# DCDC_2_rev3.net
KiCad netlist of a schematic drawn in Altium Designer
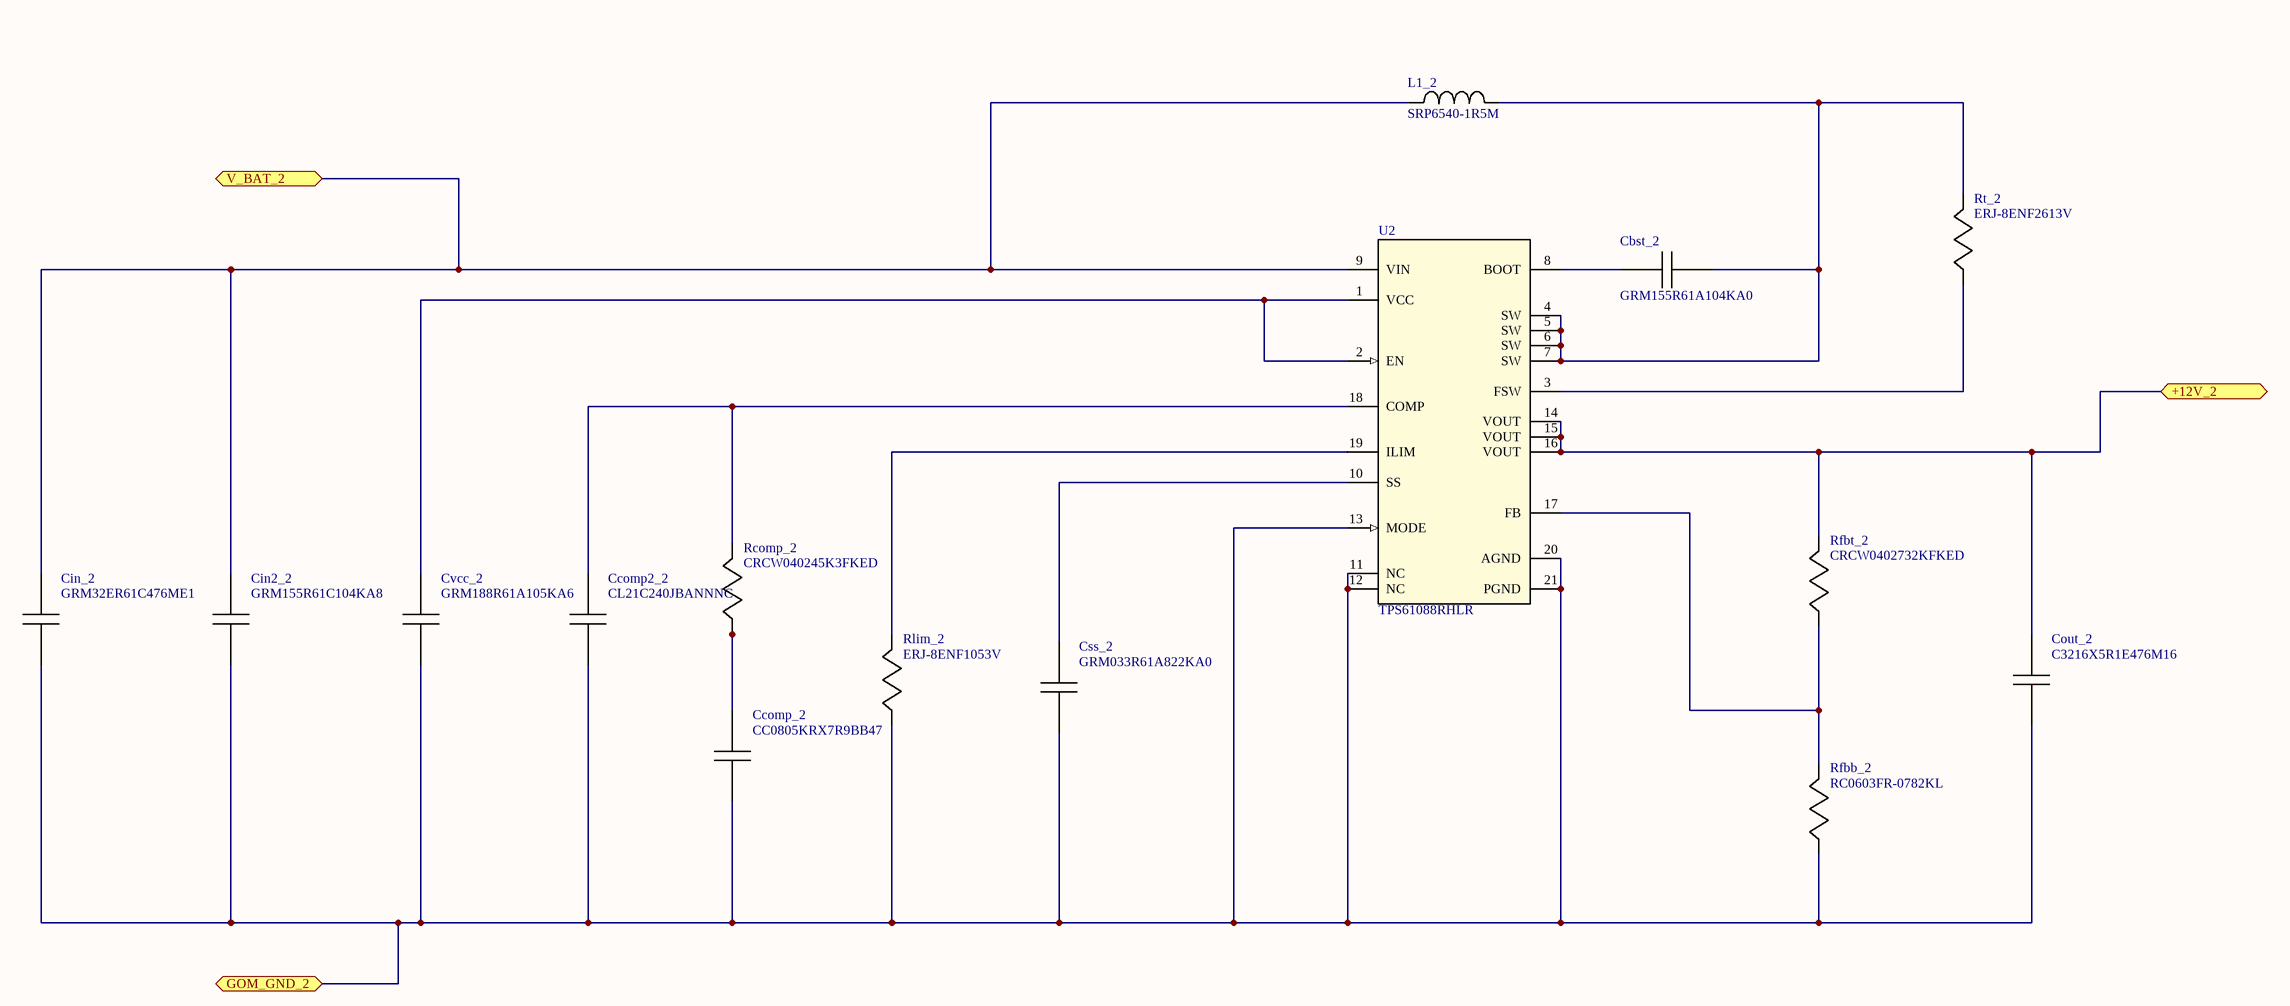
[diagram p0: DCDC_2_rev3.schdoc]

(export (version "E")
  (design (tool "Eeschema 10.0.6"))
  (components
    (comp (ref "Cbst_2")
      (value "GRM155R61A104KA0")
      (footprint "0402")
      (description "Imported")
      (fields (field (name "MANUFACTURER_PART_NUMBER") "GRM155R61A104KA01D"))
      (libsource (lib "2016-03-14_16-10-16") (part "GRM155R61A104KA0"))
    )
    (comp (ref "Ccomp2_2")
      (value "CL21C240JBANNNC")
      (footprint "0805")
      (description "Imported")
      (libsource (lib "2016-03-14_16-10-16") (part "CL21C240JBANNNC"))
    )
    (comp (ref "Ccomp_2")
      (value "CC0805KRX7R9BB47")
      (footprint "0805")
      (description "Imported")
      (fields (field (name "MANUFACTURER_PART_NUMBER") "CC0805KRX7R9BB471"))
      (libsource (lib "2016-03-14_16-10-16") (part "CC0805KRX7R9BB47"))
    )
    (comp (ref "Cin2_2")
      (value "GRM155R61C104KA8")
      (footprint "0402")
      (description "Imported")
      (fields (field (name "MANUFACTURER_PART_NUMBER") "GRM155R61C104KA88D"))
      (libsource (lib "2016-03-14_16-10-16") (part "GRM155R61C104KA8"))
    )
    (comp (ref "Cin_2")
      (value "GRM32ER61C476ME1")
      (footprint "1210_280")
      (description "Imported")
      (fields (field (name "MANUFACTURER_PART_NUMBER") "GRM32ER61C476ME15L"))
      (libsource (lib "2016-03-14_16-10-16") (part "GRM32ER61C476ME1"))
    )
    (comp (ref "Cout_2")
      (value "C3216X5R1E476M16")
      (footprint "1206_190")
      (description "Imported")
      (fields (field (name "MANUFACTURER_PART_NUMBER") "C3216X5R1E476M160AC"))
      (libsource (lib "2016-03-14_16-10-16") (part "C3216X5R1E476M16"))
    )
    (comp (ref "Css_2")
      (value "GRM033R61A822KA0")
      (footprint "0201")
      (description "Imported")
      (fields (field (name "MANUFACTURER_PART_NUMBER") "GRM033R61A822KA01D"))
      (libsource (lib "2016-03-14_16-10-16") (part "GRM033R61A822KA0"))
    )
    (comp (ref "Cvcc_2")
      (value "GRM188R61A105KA6")
      (footprint "0603")
      (description "Imported")
      (fields (field (name "MANUFACTURER_PART_NUMBER") "GRM188R61A105KA61D"))
      (libsource (lib "2016-03-14_16-10-16") (part "GRM188R61A105KA6"))
    )
    (comp (ref "L1_2")
      (value "SRP6540-1R5M")
      (footprint "SRP6540")
      (description "Imported")
      (fields (field (name "MANUFACTURER") "Bourns"))
      (libsource (lib "2016-03-14_16-10-16") (part "SRP6540-1R5M"))
    )
    (comp (ref "Rcomp_2")
      (value "CRCW040245K3FKED")
      (footprint "0402")
      (description "Imported")
      (libsource (lib "2016-03-14_16-10-16") (part "CRCW040245K3FKED"))
    )
    (comp (ref "Rfbb_2")
      (value "RC0603FR-0782KL")
      (footprint "0603")
      (description "Imported")
      (libsource (lib "2016-03-14_16-10-16") (part "RC0603FR-0782KL"))
    )
    (comp (ref "Rfbt_2")
      (value "CRCW0402732KFKED")
      (footprint "0402")
      (description "Imported")
      (libsource (lib "2016-03-14_16-10-16") (part "CRCW0402732KFKED"))
    )
    (comp (ref "Rlim_2")
      (value "ERJ-8ENF1053V")
      (footprint "1206")
      (description "Imported")
      (libsource (lib "2016-03-14_16-10-16") (part "ERJ-8ENF1053V"))
    )
    (comp (ref "Rt_2")
      (value "ERJ-8ENF2613V")
      (footprint "1206")
      (description "Imported")
      (libsource (lib "2016-03-14_16-10-16") (part "ERJ-8ENF2613V"))
    )
    (comp (ref "U2")
      (value "TPS61088RHLR")
      (footprint "RHL0020A")
      (description "Imported")
      (fields
        (field (name "ALTERNATE PARTNUMBER") "TPS61088RHLT")
        (field (name "MANUFACTURER") "Texas Instruments")
      )
      (libsource (lib "2016-03-14_16-10-16") (part "TPS61088RHLR"))
    )
  )
  (nets
    (net (code "1") (name "/+12V_2") (class "Default")
      (node (ref "Cout_2") (pin "1") (pinfunction "1_1") (pintype "passive"))
      (node (ref "Rfbt_2") (pin "1") (pinfunction "1_1") (pintype "passive"))
      (node (ref "U2") (pin "14") (pinfunction "VOUT_14") (pintype "passive"))
      (node (ref "U2") (pin "15") (pinfunction "VOUT_15") (pintype "passive"))
      (node (ref "U2") (pin "16") (pinfunction "VOUT_16") (pintype "passive"))
    )
    (net (code "2") (name "/GOM_GND_2") (class "Default")
      (node (ref "Ccomp2_2") (pin "2") (pinfunction "2_2") (pintype "passive"))
      (node (ref "Ccomp_2") (pin "2") (pinfunction "2_2") (pintype "passive"))
      (node (ref "Cin2_2") (pin "2") (pinfunction "2_2") (pintype "passive"))
      (node (ref "Cin_2") (pin "2") (pinfunction "2_2") (pintype "passive"))
      (node (ref "Cout_2") (pin "2") (pinfunction "2_2") (pintype "passive"))
      (node (ref "Css_2") (pin "2") (pinfunction "2_2") (pintype "passive"))
      (node (ref "Cvcc_2") (pin "2") (pinfunction "2_2") (pintype "passive"))
      (node (ref "Rfbb_2") (pin "2") (pinfunction "2_2") (pintype "passive"))
      (node (ref "Rlim_2") (pin "2") (pinfunction "2_2") (pintype "passive"))
      (node (ref "U2") (pin "11") (pinfunction "NC_11") (pintype "passive"))
      (node (ref "U2") (pin "12") (pinfunction "NC_12") (pintype "passive"))
      (node (ref "U2") (pin "13") (pinfunction "MODE_13") (pintype "input"))
      (node (ref "U2") (pin "20") (pinfunction "AGND_20") (pintype "passive"))
      (node (ref "U2") (pin "21") (pinfunction "PGND_21") (pintype "passive"))
    )
    (net (code "3") (name "/V_BAT_2") (class "Default")
      (node (ref "Cin2_2") (pin "1") (pinfunction "1_1") (pintype "passive"))
      (node (ref "Cin_2") (pin "1") (pinfunction "1_1") (pintype "passive"))
      (node (ref "L1_2") (pin "1") (pinfunction "1_1") (pintype "passive"))
      (node (ref "U2") (pin "9") (pinfunction "VIN_9") (pintype "passive"))
    )
    (net (code "4") (name "Net-(Cbst_2-Pad1)") (class "Default")
      (node (ref "Cbst_2") (pin "1") (pinfunction "1_1") (pintype "passive"))
      (node (ref "L1_2") (pin "2") (pinfunction "2_2") (pintype "passive"))
      (node (ref "Rt_2") (pin "1") (pinfunction "1_1") (pintype "passive"))
      (node (ref "U2") (pin "4") (pinfunction "SW_4") (pintype "power_in"))
      (node (ref "U2") (pin "5") (pinfunction "SW_5") (pintype "power_in"))
      (node (ref "U2") (pin "6") (pinfunction "SW_6") (pintype "power_in"))
      (node (ref "U2") (pin "7") (pinfunction "SW_7") (pintype "power_in"))
    )
    (net (code "5") (name "Net-(Ccomp_2-Pad1)") (class "Default")
      (node (ref "Ccomp_2") (pin "1") (pinfunction "1_1") (pintype "passive"))
      (node (ref "Rcomp_2") (pin "2") (pinfunction "2_2") (pintype "passive"))
    )
    (net (code "6") (name "Net-(U2-BOOT)") (class "Default")
      (node (ref "Cbst_2") (pin "2") (pinfunction "2_2") (pintype "passive"))
      (node (ref "U2") (pin "8") (pinfunction "BOOT_8") (pintype "power_in"))
    )
    (net (code "7") (name "Net-(U2-COMP)") (class "Default")
      (node (ref "Ccomp2_2") (pin "1") (pinfunction "1_1") (pintype "passive"))
      (node (ref "Rcomp_2") (pin "1") (pinfunction "1_1") (pintype "passive"))
      (node (ref "U2") (pin "18") (pinfunction "COMP_18") (pintype "passive"))
    )
    (net (code "8") (name "Net-(U2-EN)") (class "Default")
      (node (ref "Cvcc_2") (pin "1") (pinfunction "1_1") (pintype "passive"))
      (node (ref "U2") (pin "1") (pinfunction "VCC_1") (pintype "power_in"))
      (node (ref "U2") (pin "2") (pinfunction "EN_2") (pintype "input"))
    )
    (net (code "9") (name "Net-(U2-FB)") (class "Default")
      (node (ref "Rfbb_2") (pin "1") (pinfunction "1_1") (pintype "passive"))
      (node (ref "Rfbt_2") (pin "2") (pinfunction "2_2") (pintype "passive"))
      (node (ref "U2") (pin "17") (pinfunction "FB_17") (pintype "passive"))
    )
    (net (code "10") (name "Net-(U2-FSW)") (class "Default")
      (node (ref "Rt_2") (pin "2") (pinfunction "2_2") (pintype "passive"))
      (node (ref "U2") (pin "3") (pinfunction "FSW_3") (pintype "passive"))
    )
    (net (code "11") (name "Net-(U2-ILIM)") (class "Default")
      (node (ref "Rlim_2") (pin "1") (pinfunction "1_1") (pintype "passive"))
      (node (ref "U2") (pin "19") (pinfunction "ILIM_19") (pintype "passive"))
    )
    (net (code "12") (name "Net-(U2-SS)") (class "Default")
      (node (ref "Css_2") (pin "1") (pinfunction "1_1") (pintype "passive"))
      (node (ref "U2") (pin "10") (pinfunction "SS_10") (pintype "passive"))
    )
  )
)
